# Powerswitch.net
KiCad netlist of a schematic drawn in Altium Designer
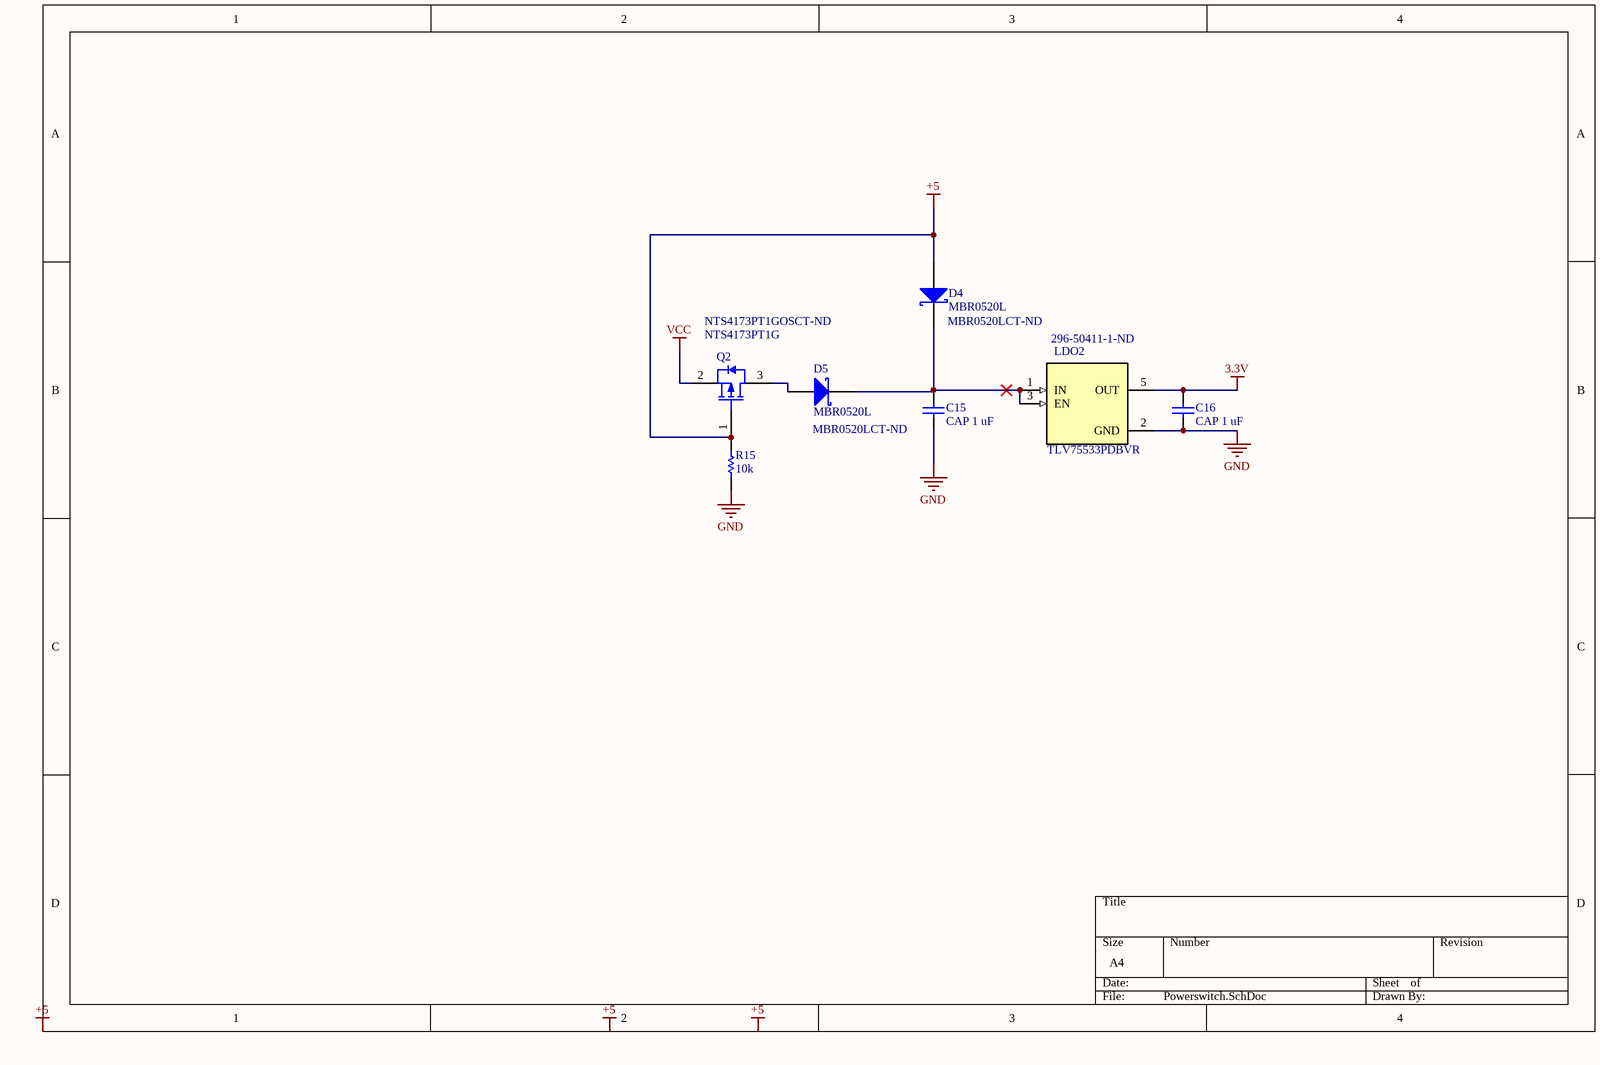
[diagram p0: Powerswitch.SchDoc]

(export (version "E")
  (design (tool "Eeschema 10.0.6"))
  (components
    (comp (ref "C15")
      (value "CAP 1 uF")
      (footprint "CL10A105KB8NNNC")
      (description "Capacitor")
      (fields (field (name "PUBLISHER") "Altium Limited"))
      (libsource (lib "Miscellaneous Devices") (part "Cap"))
    )
    (comp (ref "C16")
      (value "CAP 1 uF")
      (footprint "CL10A105KB8NNNC")
      (description "Capacitor")
      (fields (field (name "PUBLISHER") "Altium Limited"))
      (libsource (lib "Miscellaneous Devices") (part "Cap"))
    )
    (comp (ref "D4")
      (value "MBR0520L")
      (footprint "ON_Semi_CASE_425_0")
      (description "Schottky Diode")
      (fields
        (field (name "MANUFACTURER") "ON Semiconductor / Fairchild")
        (field (name "SUPPLIER PART NUMBER 1") "MBR0520LCT-ND")
      )
      (libsource (lib "MBR0520L") (part "MBR0520L"))
    )
    (comp (ref "D5")
      (value "MBR0520L")
      (footprint "ON_Semi_CASE_425_0")
      (description "Schottky Diode")
      (fields
        (field (name "MANUFACTURER") "ON Semiconductor / Fairchild")
        (field (name "SUPPLIER PART NUMBER 1") "MBR0520LCT-ND")
      )
      (libsource (lib "MBR0520L") (part "MBR0520L"))
    )
    (comp (ref "LDO2")
      (value "TLV75533PDBVR")
      (footprint "SOT95P280X145-5N")
      (description "500mA Low-IQ Small-Size Low-Dropout _LDO_ Regulator 5-SOT-23 -40 to 125")
      (fields
        (field (name "MF") "Texas Instruments")
        (field (name "SUPPLIER PART NUMBER 1") "296-50411-1-ND")
      )
      (libsource (lib "TLV75533PDBVR") (part "TLV75533PDBVR"))
    )
    (comp (ref "Q2")
      (value "NTS4173PT1G")
      (footprint "ONSC-SC-70-3-419-04_V")
      (description "Power MOSFET, -30 V, -1.3 A, Single P-Channel, 3-Pin SC-70, Pb-Free, Tape and Reel")
      (fields
        (field (name "MANUFACTURER") "On Semiconductor")
        (field (name "SUPPLIER PART NUMBER 1") "NTS4173PT1GOSCT-ND")
      )
      (libsource (lib "Altium Content Vault") (part "ONSC-PMOS-G1S2D3-3_D"))
    )
    (comp (ref "R15")
      (value "10k")
      (footprint "RK73H1JTTD1002F")
      (description "Resistor")
      (fields (field (name "PUBLISHER") "Altium Limited"))
      (libsource (lib "Miscellaneous Devices") (part "Res1"))
    )
  )
  (nets
    (net (code "1") (name "+5") (class "Default")
      (node (ref "D4") (pin "1") (pinfunction "A_1") (pintype "passive"))
      (node (ref "Q2") (pin "1") (pinfunction "G_1") (pintype "passive"))
      (node (ref "R15") (pin "2") (pinfunction "2_2") (pintype "passive"))
    )
    (net (code "2") (name "3.3V") (class "Default")
      (node (ref "C16") (pin "1") (pinfunction "1_1") (pintype "passive"))
      (node (ref "LDO2") (pin "5") (pinfunction "OUT_5") (pintype "power_in"))
    )
    (net (code "3") (name "GND") (class "Default")
      (node (ref "C15") (pin "2") (pinfunction "2_2") (pintype "passive"))
      (node (ref "C16") (pin "2") (pinfunction "2_2") (pintype "passive"))
      (node (ref "LDO2") (pin "2") (pinfunction "GND_2") (pintype "power_in"))
      (node (ref "R15") (pin "1") (pinfunction "1_1") (pintype "passive"))
    )
    (net (code "4") (name "Net-(D4-K)") (class "Default")
      (node (ref "C15") (pin "1") (pinfunction "1_1") (pintype "passive"))
      (node (ref "D4") (pin "2") (pinfunction "K_2") (pintype "passive"))
      (node (ref "D5") (pin "2") (pinfunction "K_2") (pintype "passive"))
      (node (ref "LDO2") (pin "1") (pinfunction "IN_1") (pintype "input"))
      (node (ref "LDO2") (pin "3") (pinfunction "EN_3") (pintype "input"))
    )
    (net (code "5") (name "Net-(D5-A)") (class "Default")
      (node (ref "D5") (pin "1") (pinfunction "A_1") (pintype "passive"))
      (node (ref "Q2") (pin "3") (pinfunction "D_3") (pintype "passive"))
    )
    (net (code "6") (name "VCC") (class "Default")
      (node (ref "Q2") (pin "2") (pinfunction "S_2") (pintype "passive"))
    )
  )
)
